# Logic_controller.net
KiCad netlist of a schematic drawn in Altium Designer
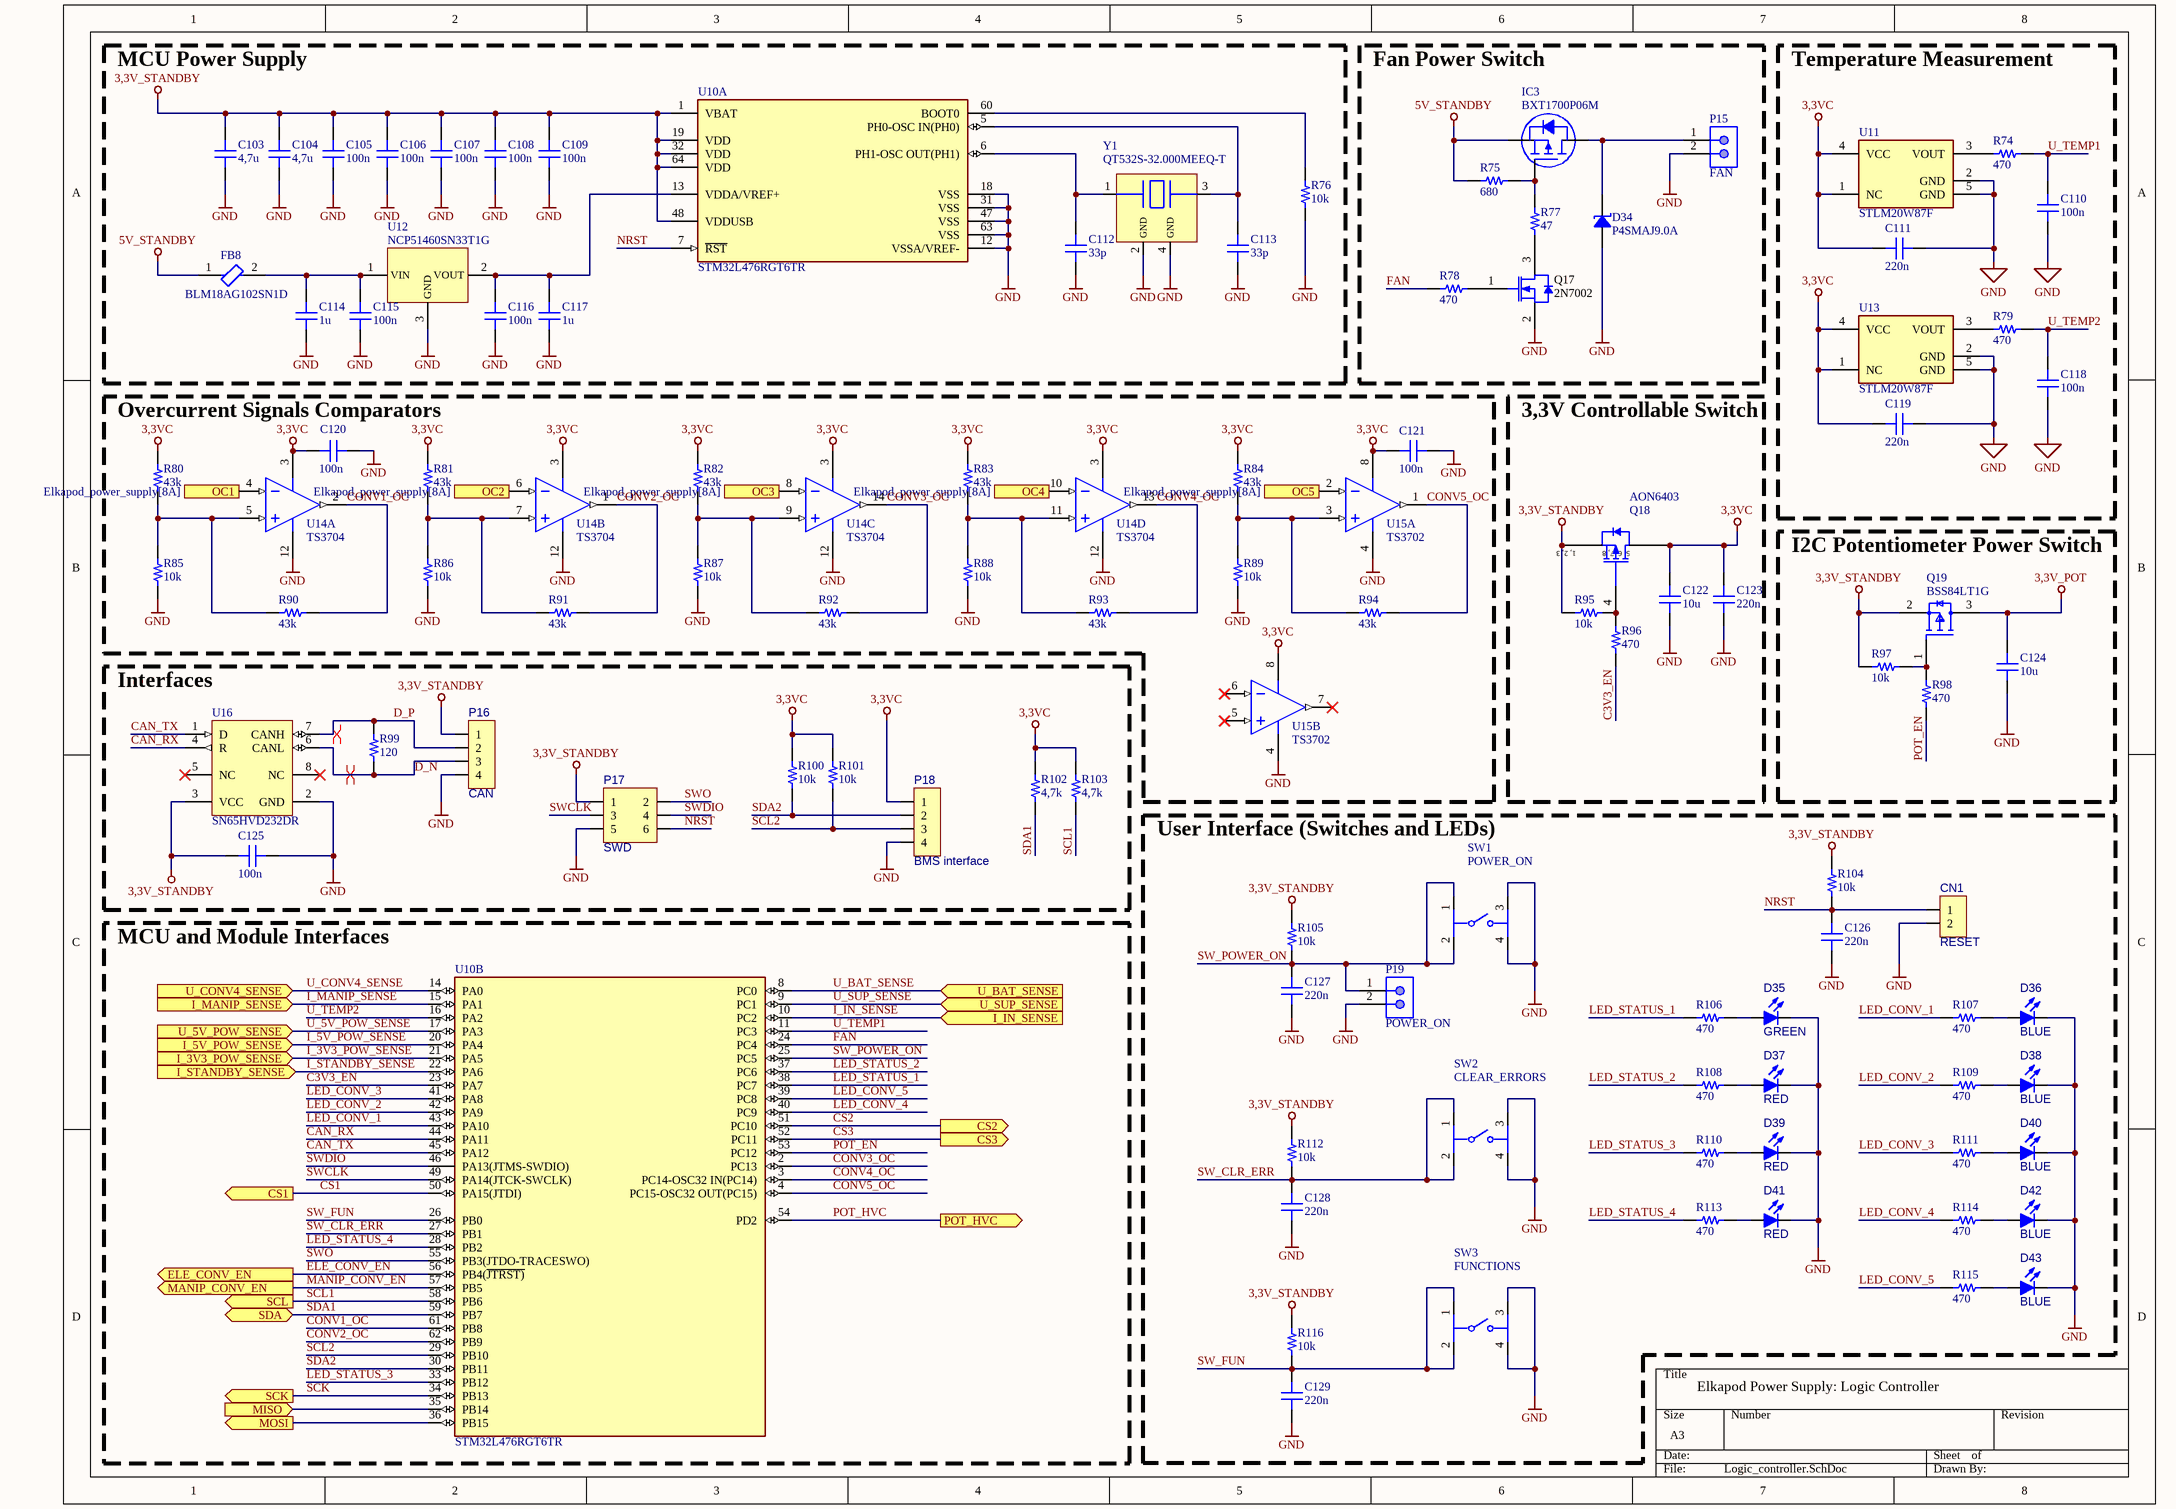
[diagram p0: Logic_controller.SchDoc]

(export (version "E")
  (design (tool "Eeschema 10.0.6"))
  (components
    (comp (ref "C103")
      (value "4,7u")
      (footprint "CAP 0603_1608")
      (description "CAP CER 4,7uF 25V X5R 0603")
      (fields (field (name "PART NUMBER") "C0603C272F3GAC7867") (field (name "MANUFACTURER") "KEMET"))
      (libsource (lib "Celestial Altium Library - altium_library") (part "Capacitor"))
    )
    (comp (ref "C104")
      (value "4,7u")
      (footprint "CAP 0603_1608")
      (description "CAP CER 4,7uF 25V X5R 0603")
      (fields (field (name "PART NUMBER") "C0603C272F3GAC7867") (field (name "MANUFACTURER") "KEMET"))
      (libsource (lib "Celestial Altium Library - altium_library") (part "Capacitor"))
    )
    (comp (ref "C105")
      (value "100n")
      (footprint "CAP 0603_1608")
      (description "CAP CER 100nF 25V X5R 0603")
      (fields (field (name "PART NUMBER") "C0603C272F3GAC7867") (field (name "MANUFACTURER") "KEMET"))
      (libsource (lib "Celestial Altium Library - altium_library") (part "Capacitor"))
    )
    (comp (ref "C106")
      (value "100n")
      (footprint "CAP 0603_1608")
      (description "CAP CER 100nF 25V X5R 0603")
      (fields (field (name "PART NUMBER") "C0603C272F3GAC7867") (field (name "MANUFACTURER") "KEMET"))
      (libsource (lib "Celestial Altium Library - altium_library") (part "Capacitor"))
    )
    (comp (ref "C107")
      (value "100n")
      (footprint "CAP 0603_1608")
      (description "CAP CER 100nF 25V X5R 0603")
      (fields (field (name "PART NUMBER") "C0603C272F3GAC7867") (field (name "MANUFACTURER") "KEMET"))
      (libsource (lib "Celestial Altium Library - altium_library") (part "Capacitor"))
    )
    (comp (ref "C108")
      (value "100n")
      (footprint "CAP 0603_1608")
      (description "CAP CER 100nF 25V X5R 0603")
      (fields (field (name "PART NUMBER") "C0603C272F3GAC7867") (field (name "MANUFACTURER") "KEMET"))
      (libsource (lib "Celestial Altium Library - altium_library") (part "Capacitor"))
    )
    (comp (ref "C109")
      (value "100n")
      (footprint "CAP 0603_1608")
      (description "CAP CER 100nF 25V X5R 0603")
      (fields (field (name "PART NUMBER") "C0603C272F3GAC7867") (field (name "MANUFACTURER") "KEMET"))
      (libsource (lib "Celestial Altium Library - altium_library") (part "Capacitor"))
    )
    (comp (ref "C110")
      (value "100n")
      (footprint "CAP 0603_1608")
      (description "CAP CER 100nF 25V X5R 0603")
      (fields (field (name "PART NUMBER") "C0603C272F3GAC7867") (field (name "MANUFACTURER") "KEMET"))
      (libsource (lib "Celestial Altium Library - altium_library") (part "Capacitor"))
    )
    (comp (ref "C111")
      (value "220n")
      (footprint "CAP 0603_1608")
      (description "CAP CER 220nF 25V X5R 0603")
      (fields (field (name "PART NUMBER") "C0603C272F3GAC7867") (field (name "MANUFACTURER") "KEMET"))
      (libsource (lib "Celestial Altium Library - altium_library") (part "Capacitor"))
    )
    (comp (ref "C112")
      (value "33p")
      (footprint "CAP 0603_1608")
      (description "CAP CER 33pF 50V G0C 0603")
      (fields (field (name "PART NUMBER") "C0603C272F3GAC7867") (field (name "MANUFACTURER") "KEMET"))
      (libsource (lib "Celestial Altium Library - altium_library") (part "Capacitor"))
    )
    (comp (ref "C113")
      (value "33p")
      (footprint "CAP 0603_1608")
      (description "CAP CER 33pF 50V G0C 0603")
      (fields (field (name "PART NUMBER") "C0603C272F3GAC7867") (field (name "MANUFACTURER") "KEMET"))
      (libsource (lib "Celestial Altium Library - altium_library") (part "Capacitor"))
    )
    (comp (ref "C114")
      (value "1u")
      (footprint "CAP 0603_1608")
      (description "CAP CER 1uF 16V X5R 0603")
      (fields (field (name "PART NUMBER") "C0603C272F3GAC7867") (field (name "MANUFACTURER") "KEMET"))
      (libsource (lib "Celestial Altium Library - altium_library") (part "Capacitor"))
    )
    (comp (ref "C115")
      (value "100n")
      (footprint "CAP 0603_1608")
      (description "CAP CER 100nF 25V X5R 0603")
      (fields (field (name "PART NUMBER") "C0603C272F3GAC7867") (field (name "MANUFACTURER") "KEMET"))
      (libsource (lib "Celestial Altium Library - altium_library") (part "Capacitor"))
    )
    (comp (ref "C116")
      (value "100n")
      (footprint "CAP 0603_1608")
      (description "CAP CER 100nF 25V X5R 0603")
      (fields (field (name "PART NUMBER") "C0603C272F3GAC7867") (field (name "MANUFACTURER") "KEMET"))
      (libsource (lib "Celestial Altium Library - altium_library") (part "Capacitor"))
    )
    (comp (ref "C117")
      (value "1u")
      (footprint "CAP 0603_1608")
      (description "CAP CER 1uF 16V X5R 0603")
      (fields (field (name "PART NUMBER") "C0603C272F3GAC7867") (field (name "MANUFACTURER") "KEMET"))
      (libsource (lib "Celestial Altium Library - altium_library") (part "Capacitor"))
    )
    (comp (ref "C118")
      (value "100n")
      (footprint "CAP 0603_1608")
      (description "CAP CER 100nF 25V X5R 0603")
      (fields (field (name "PART NUMBER") "C0603C272F3GAC7867") (field (name "MANUFACTURER") "KEMET"))
      (libsource (lib "Celestial Altium Library - altium_library") (part "Capacitor"))
    )
    (comp (ref "C119")
      (value "220n")
      (footprint "CAP 0603_1608")
      (description "CAP CER 220nF 25V X5R 0603")
      (fields (field (name "PART NUMBER") "C0603C272F3GAC7867") (field (name "MANUFACTURER") "KEMET"))
      (libsource (lib "Celestial Altium Library - altium_library") (part "Capacitor"))
    )
    (comp (ref "C120")
      (value "100n")
      (footprint "CAP 0603_1608")
      (description "CAP CER 100nF 25V X5R 0603")
      (fields (field (name "PART NUMBER") "C0603C272F3GAC7867") (field (name "MANUFACTURER") "KEMET"))
      (libsource (lib "Celestial Altium Library - altium_library") (part "Capacitor"))
    )
    (comp (ref "C121")
      (value "100n")
      (footprint "CAP 0603_1608")
      (description "CAP CER 100nF 25V X5R 0603")
      (fields (field (name "PART NUMBER") "C0603C272F3GAC7867") (field (name "MANUFACTURER") "KEMET"))
      (libsource (lib "Celestial Altium Library - altium_library") (part "Capacitor"))
    )
    (comp (ref "C122")
      (value "10u")
      (footprint "CAP 0603_1608")
      (description "CAP CER 10uF 35V X5R 0603")
      (fields (field (name "PART NUMBER") "C0603C272F3GAC7867") (field (name "MANUFACTURER") "KEMET"))
      (libsource (lib "Celestial Altium Library - altium_library") (part "Capacitor"))
    )
    (comp (ref "C123")
      (value "220n")
      (footprint "CAP 0603_1608")
      (description "CAP CER 220nF 25V X5R 0603")
      (fields (field (name "PART NUMBER") "C0603C272F3GAC7867") (field (name "MANUFACTURER") "KEMET"))
      (libsource (lib "Celestial Altium Library - altium_library") (part "Capacitor"))
    )
    (comp (ref "C124")
      (value "10u")
      (footprint "CAP 0603_1608")
      (description "CAP CER 10uF 35V X5R 0603")
      (fields (field (name "PART NUMBER") "C0603C272F3GAC7867") (field (name "MANUFACTURER") "KEMET"))
      (libsource (lib "Celestial Altium Library - altium_library") (part "Capacitor"))
    )
    (comp (ref "C125")
      (value "100n")
      (footprint "CAP 0603_1608")
      (description "CAP CER 100nF 25V X5R 0603")
      (fields (field (name "PART NUMBER") "C0603C272F3GAC7867") (field (name "MANUFACTURER") "KEMET"))
      (libsource (lib "Celestial Altium Library - altium_library") (part "Capacitor"))
    )
    (comp (ref "C126")
      (value "220n")
      (footprint "CAP 0603_1608")
      (description "CAP CER 220nF 25V X5R 0603")
      (fields (field (name "PART NUMBER") "C0603C272F3GAC7867") (field (name "MANUFACTURER") "KEMET"))
      (libsource (lib "Celestial Altium Library - altium_library") (part "Capacitor"))
    )
    (comp (ref "C127")
      (value "220n")
      (footprint "CAP 0603_1608")
      (description "CAP CER 220nF 25V X5R 0603")
      (fields (field (name "PART NUMBER") "C0603C272F3GAC7867") (field (name "MANUFACTURER") "KEMET"))
      (libsource (lib "Celestial Altium Library - altium_library") (part "Capacitor"))
    )
    (comp (ref "C128")
      (value "220n")
      (footprint "CAP 0603_1608")
      (description "CAP CER 220nF 25V X5R 0603")
      (fields (field (name "PART NUMBER") "C0603C272F3GAC7867") (field (name "MANUFACTURER") "KEMET"))
      (libsource (lib "Celestial Altium Library - altium_library") (part "Capacitor"))
    )
    (comp (ref "C129")
      (value "220n")
      (footprint "CAP 0603_1608")
      (description "CAP CER 220nF 25V X5R 0603")
      (fields (field (name "PART NUMBER") "C0603C272F3GAC7867") (field (name "MANUFACTURER") "KEMET"))
      (libsource (lib "Celestial Altium Library - altium_library") (part "Capacitor"))
    )
    (comp (ref "CN1") (value "RESET") (footprint "GP_2x1") (libsource (lib "goldpin_male") (part "CN_2x1")))
    (comp (ref "D34")
      (value "P4SMAJ9.0A")
      (footprint "DO214AC SMA")
      (description "TVS DIODE 9VDC DO214AC")
      (libsource (lib "Celestial Altium Library - altium_library") (part "DIODE TVS UNI"))
    )
    (comp (ref "D35")
      (value "GREEN")
      (footprint "LED0805B")
      (description "GREEN LED")
      (libsource (lib "leds") (part "LED_BLUE"))
    )
    (comp (ref "D36")
      (value "BLUE")
      (footprint "LED0805B")
      (description "BLUE LED")
      (libsource (lib "leds") (part "LED_BLUE"))
    )
    (comp (ref "D37")
      (value "RED")
      (footprint "LED0805B")
      (description "RED LED")
      (libsource (lib "leds") (part "LED_BLUE"))
    )
    (comp (ref "D38")
      (value "BLUE")
      (footprint "LED0805B")
      (description "BLUE LED")
      (libsource (lib "leds") (part "LED_BLUE"))
    )
    (comp (ref "D39")
      (value "RED")
      (footprint "LED0805B")
      (description "RED LED")
      (libsource (lib "leds") (part "LED_BLUE"))
    )
    (comp (ref "D40")
      (value "BLUE")
      (footprint "LED0805B")
      (description "BLUE LED")
      (libsource (lib "leds") (part "LED_BLUE"))
    )
    (comp (ref "D41")
      (value "RED")
      (footprint "LED0805B")
      (description "RED LED")
      (libsource (lib "leds") (part "LED_BLUE"))
    )
    (comp (ref "D42")
      (value "BLUE")
      (footprint "LED0805B")
      (description "BLUE LED")
      (libsource (lib "leds") (part "LED_BLUE"))
    )
    (comp (ref "D43")
      (value "BLUE")
      (footprint "LED0805B")
      (description "BLUE LED")
      (libsource (lib "leds") (part "LED_BLUE"))
    )
    (comp (ref "FB8")
      (value "BLM18AG102SN1D")
      (footprint "FP-BLM18-0_15-t0_8-MFG")
      (description "Chip Ferrite Bead, 0603, 1000Ω @ 100MHz, 0.5Ω, 25%, 450mA")
      (fields (field (name "TOLERANCE") "25%"))
      (libsource (lib "Altium Content Vault") (part "5f30dd21d616792df468990f7003faa"))
    )
    (comp (ref "IC3")
      (value "BXT1700P06M")
      (footprint "ON SEMI SOT-23-3")
      (description "MOSFET P-CH 60V 2.8A SOT-23-3")
      (libsource (lib "Celestial Altium Library - altium_library") (part "ON SEMI MOSFET P-CH SOT-23-3"))
    )
    (comp (ref "P15")
      (value "FAN")
      (footprint "MOLX-22-23-2021_V")
      (fields (field (name "PARTNUMBER") "22-23-2021"))
      (libsource (lib "Altium Content Vault") (part "CN-1P-M-R2"))
    )
    (comp (ref "P16")
      (value "CAN")
      (footprint "KK/2.54/4")
      (description "Connector: PCB-cable; KK; socket; male; PIN:4; straight/right-angle; tinned; THT")
      (libsource (lib "kk") (part "CN_4x1"))
    )
    (comp (ref "P17") (value "SWD") (footprint "GP_3x2") (libsource (lib "goldpin_male") (part "CN_3x2")))
    (comp (ref "P18")
      (value "BMS interface")
      (footprint "KK/2.54/4")
      (description "Connector: PCB-cable; KK; socket; male; PIN:4; straight/right-angle; tinned; THT")
      (libsource (lib "kk") (part "CN_4x1"))
    )
    (comp (ref "P19")
      (value "POWER_ON")
      (footprint "MOLX-22-23-2021_V")
      (fields (field (name "PARTNUMBER") "22-23-2021"))
      (libsource (lib "Altium Content Vault") (part "CN-1P-M-R2"))
    )
    (comp (ref "Q17")
      (value "2N7002")
      (footprint "INF-PG-SOT23_M")
      (fields (field (name "MANUFACTURER") "Infineon"))
      (libsource (lib "Altium Content Vault") (part "INF-NDMOS-GSD-3"))
    )
    (comp (ref "Q18")
      (value "AON6403")
      (footprint "DFN5x6")
      (description "P-MOSFET; 67A; 30V; DFN5x6")
      (libsource (lib "My_transistors") (part "AON6403"))
    )
    (comp (ref "Q19")
      (value "BSS84LT1G")
      (footprint "FP-318-08-IPC_A")
      (description "MOSFET P-CH 50V 130MA SOT-23")
      (libsource (lib "Altium Content Vault") (part "1317a8eff0fddff9cd18bdaa032127a"))
    )
    (comp (ref "R74")
      (value "470")
      (footprint "RES 0603_1608")
      (description "RES 470 OHM 1% 0,1W 0603")
      (fields
        (field (name "PART NUMBER") "RNCS0603BKE10K0")
        (field (name "MANUFACTURER") "Stackpole Electronics Inc")
      )
      (libsource (lib "Celestial Altium Library - altium_library") (part "Resistor"))
    )
    (comp (ref "R75")
      (value "680")
      (footprint "RES 0603_1608")
      (description "RES 680 OHM 1% 0,1W 0603")
      (fields
        (field (name "PART NUMBER") "RNCS0603BKE10K0")
        (field (name "MANUFACTURER") "Stackpole Electronics Inc")
      )
      (libsource (lib "Celestial Altium Library - altium_library") (part "Resistor"))
    )
    (comp (ref "R76")
      (value "10k")
      (footprint "RES 0603_1608")
      (description "RES 10K OHM 1% 0,1W 0603")
      (fields
        (field (name "PART NUMBER") "RNCS0603BKE10K0")
        (field (name "MANUFACTURER") "Stackpole Electronics Inc")
      )
      (libsource (lib "Celestial Altium Library - altium_library") (part "Resistor"))
    )
    (comp (ref "R77")
      (value "47")
      (footprint "RES 0603_1608")
      (description "RES 47 OHM 1% 0,1W 0603")
      (fields
        (field (name "PART NUMBER") "RNCS0603BKE10K0")
        (field (name "MANUFACTURER") "Stackpole Electronics Inc")
      )
      (libsource (lib "Celestial Altium Library - altium_library") (part "Resistor"))
    )
    (comp (ref "R78")
      (value "470")
      (footprint "RES 0603_1608")
      (description "RES 470 OHM 1% 0,1W 0603")
      (fields
        (field (name "PART NUMBER") "RNCS0603BKE10K0")
        (field (name "MANUFACTURER") "Stackpole Electronics Inc")
      )
      (libsource (lib "Celestial Altium Library - altium_library") (part "Resistor"))
    )
    (comp (ref "R79")
      (value "470")
      (footprint "RES 0603_1608")
      (description "RES 470 OHM 1% 0,1W 0603")
      (fields
        (field (name "PART NUMBER") "RNCS0603BKE10K0")
        (field (name "MANUFACTURER") "Stackpole Electronics Inc")
      )
      (libsource (lib "Celestial Altium Library - altium_library") (part "Resistor"))
    )
    (comp (ref "R80")
      (value "43k")
      (footprint "RES 0603_1608")
      (description "RES 43K OHM 1% 0,1W 0603")
      (fields
        (field (name "PART NUMBER") "RNCS0603BKE10K0")
        (field (name "MANUFACTURER") "Stackpole Electronics Inc")
      )
      (libsource (lib "Celestial Altium Library - altium_library") (part "Resistor"))
    )
    (comp (ref "R81")
      (value "43k")
      (footprint "RES 0603_1608")
      (description "RES 43K OHM 1% 0,1W 0603")
      (fields
        (field (name "PART NUMBER") "RNCS0603BKE10K0")
        (field (name "MANUFACTURER") "Stackpole Electronics Inc")
      )
      (libsource (lib "Celestial Altium Library - altium_library") (part "Resistor"))
    )
    (comp (ref "R82")
      (value "43k")
      (footprint "RES 0603_1608")
      (description "RES 43K OHM 1% 0,1W 0603")
      (fields
        (field (name "PART NUMBER") "RNCS0603BKE10K0")
        (field (name "MANUFACTURER") "Stackpole Electronics Inc")
      )
      (libsource (lib "Celestial Altium Library - altium_library") (part "Resistor"))
    )
    (comp (ref "R83")
      (value "43k")
      (footprint "RES 0603_1608")
      (description "RES 43K OHM 1% 0,1W 0603")
      (fields
        (field (name "PART NUMBER") "RNCS0603BKE10K0")
        (field (name "MANUFACTURER") "Stackpole Electronics Inc")
      )
      (libsource (lib "Celestial Altium Library - altium_library") (part "Resistor"))
    )
    (comp (ref "R84")
      (value "43k")
      (footprint "RES 0603_1608")
      (description "RES 43K OHM 1% 0,1W 0603")
      (fields
        (field (name "PART NUMBER") "RNCS0603BKE10K0")
        (field (name "MANUFACTURER") "Stackpole Electronics Inc")
      )
      (libsource (lib "Celestial Altium Library - altium_library") (part "Resistor"))
    )
    (comp (ref "R85")
      (value "10k")
      (footprint "RES 0603_1608")
      (description "RES 10K OHM 1% 0,1W 0603")
      (fields
        (field (name "PART NUMBER") "RNCS0603BKE10K0")
        (field (name "MANUFACTURER") "Stackpole Electronics Inc")
      )
      (libsource (lib "Celestial Altium Library - altium_library") (part "Resistor"))
    )
    (comp (ref "R86")
      (value "10k")
      (footprint "RES 0603_1608")
      (description "RES 10K OHM 1% 0,1W 0603")
      (fields
        (field (name "PART NUMBER") "RNCS0603BKE10K0")
        (field (name "MANUFACTURER") "Stackpole Electronics Inc")
      )
      (libsource (lib "Celestial Altium Library - altium_library") (part "Resistor"))
    )
    (comp (ref "R87")
      (value "10k")
      (footprint "RES 0603_1608")
      (description "RES 10K OHM 1% 0,1W 0603")
      (fields
        (field (name "PART NUMBER") "RNCS0603BKE10K0")
        (field (name "MANUFACTURER") "Stackpole Electronics Inc")
      )
      (libsource (lib "Celestial Altium Library - altium_library") (part "Resistor"))
    )
    (comp (ref "R88")
      (value "10k")
      (footprint "RES 0603_1608")
      (description "RES 10K OHM 1% 0,1W 0603")
      (fields
        (field (name "PART NUMBER") "RNCS0603BKE10K0")
        (field (name "MANUFACTURER") "Stackpole Electronics Inc")
      )
      (libsource (lib "Celestial Altium Library - altium_library") (part "Resistor"))
    )
    (comp (ref "R89")
      (value "10k")
      (footprint "RES 0603_1608")
      (description "RES 10K OHM 1% 0,1W 0603")
      (fields
        (field (name "PART NUMBER") "RNCS0603BKE10K0")
        (field (name "MANUFACTURER") "Stackpole Electronics Inc")
      )
      (libsource (lib "Celestial Altium Library - altium_library") (part "Resistor"))
    )
    (comp (ref "R90")
      (value "43k")
      (footprint "RES 0603_1608")
      (description "RES 43K OHM 1% 0,1W 0603")
      (fields
        (field (name "PART NUMBER") "RNCS0603BKE10K0")
        (field (name "MANUFACTURER") "Stackpole Electronics Inc")
      )
      (libsource (lib "Celestial Altium Library - altium_library") (part "Resistor"))
    )
    (comp (ref "R91")
      (value "43k")
      (footprint "RES 0603_1608")
      (description "RES 43K OHM 1% 0,1W 0603")
      (fields
        (field (name "PART NUMBER") "RNCS0603BKE10K0")
        (field (name "MANUFACTURER") "Stackpole Electronics Inc")
      )
      (libsource (lib "Celestial Altium Library - altium_library") (part "Resistor"))
    )
    (comp (ref "R92")
      (value "43k")
      (footprint "RES 0603_1608")
      (description "RES 43K OHM 1% 0,1W 0603")
      (fields
        (field (name "PART NUMBER") "RNCS0603BKE10K0")
        (field (name "MANUFACTURER") "Stackpole Electronics Inc")
      )
      (libsource (lib "Celestial Altium Library - altium_library") (part "Resistor"))
    )
    (comp (ref "R93")
      (value "43k")
      (footprint "RES 0603_1608")
      (description "RES 43K OHM 1% 0,1W 0603")
      (fields
        (field (name "PART NUMBER") "RNCS0603BKE10K0")
        (field (name "MANUFACTURER") "Stackpole Electronics Inc")
      )
      (libsource (lib "Celestial Altium Library - altium_library") (part "Resistor"))
    )
    (comp (ref "R94")
      (value "43k")
      (footprint "RES 0603_1608")
      (description "RES 43K OHM 1% 0,1W 0603")
      (fields
        (field (name "PART NUMBER") "RNCS0603BKE10K0")
        (field (name "MANUFACTURER") "Stackpole Electronics Inc")
      )
      (libsource (lib "Celestial Altium Library - altium_library") (part "Resistor"))
    )
    (comp (ref "R95")
      (value "10k")
      (footprint "RES 0603_1608")
      (description "RES 10K OHM 1% 0,1W 0603")
      (fields
        (field (name "PART NUMBER") "RNCS0603BKE10K0")
        (field (name "MANUFACTURER") "Stackpole Electronics Inc")
      )
      (libsource (lib "Celestial Altium Library - altium_library") (part "Resistor"))
    )
    (comp (ref "R96")
      (value "470")
      (footprint "RES 0603_1608")
      (description "RES 470 OHM 1% 0,1W 0603")
      (fields
        (field (name "PART NUMBER") "RNCS0603BKE10K0")
        (field (name "MANUFACTURER") "Stackpole Electronics Inc")
      )
      (libsource (lib "Celestial Altium Library - altium_library") (part "Resistor"))
    )
    (comp (ref "R97")
      (value "10k")
      (footprint "RES 0603_1608")
      (description "RES 10K OHM 1% 0,1W 0603")
      (fields
        (field (name "PART NUMBER") "RNCS0603BKE10K0")
        (field (name "MANUFACTURER") "Stackpole Electronics Inc")
      )
      (libsource (lib "Celestial Altium Library - altium_library") (part "Resistor"))
    )
    (comp (ref "R98")
      (value "470")
      (footprint "RES 0603_1608")
      (description "RES 470 OHM 1% 0,1W 0603")
      (fields
        (field (name "PART NUMBER") "RNCS0603BKE10K0")
        (field (name "MANUFACTURER") "Stackpole Electronics Inc")
      )
      (libsource (lib "Celestial Altium Library - altium_library") (part "Resistor"))
    )
    (comp (ref "R99")
      (value "120")
      (footprint "RES 0603_1608")
      (description "RES 120 OHM 1% 0,1W 0603")
      (fields
        (field (name "PART NUMBER") "RNCS0603BKE10K0")
        (field (name "MANUFACTURER") "Stackpole Electronics Inc")
      )
      (libsource (lib "Celestial Altium Library - altium_library") (part "Resistor"))
    )
    (comp (ref "R100")
      (value "10k")
      (footprint "RES 0603_1608")
      (description "RES 10K OHM 1% 0,1W 0603")
      (fields
        (field (name "PART NUMBER") "RNCS0603BKE10K0")
        (field (name "MANUFACTURER") "Stackpole Electronics Inc")
      )
      (libsource (lib "Celestial Altium Library - altium_library") (part "Resistor"))
    )
    (comp (ref "R101")
      (value "10k")
      (footprint "RES 0603_1608")
      (description "RES 10K OHM 1% 0,1W 0603")
      (fields
        (field (name "PART NUMBER") "RNCS0603BKE10K0")
        (field (name "MANUFACTURER") "Stackpole Electronics Inc")
      )
      (libsource (lib "Celestial Altium Library - altium_library") (part "Resistor"))
    )
    (comp (ref "R102")
      (value "4,7k")
      (footprint "RES 0603_1608")
      (description "RES 4,7K OHM 1% 0,1W 0603")
      (fields
        (field (name "PART NUMBER") "RNCS0603BKE10K0")
        (field (name "MANUFACTURER") "Stackpole Electronics Inc")
      )
      (libsource (lib "Celestial Altium Library - altium_library") (part "Resistor"))
    )
    (comp (ref "R103")
      (value "4,7k")
      (footprint "RES 0603_1608")
      (description "RES 4,7K OHM 1% 0,1W 0603")
      (fields
        (field (name "PART NUMBER") "RNCS0603BKE10K0")
        (field (name "MANUFACTURER") "Stackpole Electronics Inc")
      )
      (libsource (lib "Celestial Altium Library - altium_library") (part "Resistor"))
    )
    (comp (ref "R104")
      (value "10k")
      (footprint "RES 0603_1608")
      (description "RES 10K OHM 1% 0,1W 0603")
      (fields
        (field (name "PART NUMBER") "RNCS0603BKE10K0")
        (field (name "MANUFACTURER") "Stackpole Electronics Inc")
      )
      (libsource (lib "Celestial Altium Library - altium_library") (part "Resistor"))
    )
    (comp (ref "R105")
      (value "10k")
      (footprint "RES 0603_1608")
      (description "RES 10K OHM 1% 0,1W 0603")
      (fields
        (field (name "PART NUMBER") "RNCS0603BKE10K0")
        (field (name "MANUFACTURER") "Stackpole Electronics Inc")
      )
      (libsource (lib "Celestial Altium Library - altium_library") (part "Resistor"))
    )
    (comp (ref "R106")
      (value "470")
      (footprint "RES 0603_1608")
      (description "RES 470 OHM 1% 0,1W 0603")
      (fields
        (field (name "PART NUMBER") "RNCS0603BKE10K0")
        (field (name "MANUFACTURER") "Stackpole Electronics Inc")
      )
      (libsource (lib "Celestial Altium Library - altium_library") (part "Resistor"))
    )
    (comp (ref "R107")
      (value "470")
      (footprint "RES 0603_1608")
      (description "RES 470 OHM 1% 0,1W 0603")
      (fields
        (field (name "PART NUMBER") "RNCS0603BKE10K0")
        (field (name "MANUFACTURER") "Stackpole Electronics Inc")
      )
      (libsource (lib "Celestial Altium Library - altium_library") (part "Resistor"))
    )
    (comp (ref "R108")
      (value "470")
      (footprint "RES 0603_1608")
      (description "RES 470 OHM 1% 0,1W 0603")
      (fields
        (field (name "PART NUMBER") "RNCS0603BKE10K0")
        (field (name "MANUFACTURER") "Stackpole Electronics Inc")
      )
      (libsource (lib "Celestial Altium Library - altium_library") (part "Resistor"))
    )
    (comp (ref "R109")
      (value "470")
      (footprint "RES 0603_1608")
      (description "RES 470 OHM 1% 0,1W 0603")
      (fields
        (field (name "PART NUMBER") "RNCS0603BKE10K0")
        (field (name "MANUFACTURER") "Stackpole Electronics Inc")
      )
      (libsource (lib "Celestial Altium Library - altium_library") (part "Resistor"))
    )
    (comp (ref "R110")
      (value "470")
      (footprint "RES 0603_1608")
      (description "RES 470 OHM 1% 0,1W 0603")
      (fields
        (field (name "PART NUMBER") "RNCS0603BKE10K0")
        (field (name "MANUFACTURER") "Stackpole Electronics Inc")
      )
      (libsource (lib "Celestial Altium Library - altium_library") (part "Resistor"))
    )
    (comp (ref "R111")
      (value "470")
      (footprint "RES 0603_1608")
      (description "RES 470 OHM 1% 0,1W 0603")
      (fields
        (field (name "PART NUMBER") "RNCS0603BKE10K0")
        (field (name "MANUFACTURER") "Stackpole Electronics Inc")
      )
      (libsource (lib "Celestial Altium Library - altium_library") (part "Resistor"))
    )
    (comp (ref "R112")
      (value "10k")
      (footprint "RES 0603_1608")
      (description "RES 10K OHM 1% 0,1W 0603")
      (fields
        (field (name "PART NUMBER") "RNCS0603BKE10K0")
        (field (name "MANUFACTURER") "Stackpole Electronics Inc")
      )
      (libsource (lib "Celestial Altium Library - altium_library") (part "Resistor"))
    )
    (comp (ref "R113")
      (value "470")
      (footprint "RES 0603_1608")
      (description "RES 470 OHM 1% 0,1W 0603")
      (fields
        (field (name "PART NUMBER") "RNCS0603BKE10K0")
        (field (name "MANUFACTURER") "Stackpole Electronics Inc")
      )
      (libsource (lib "Celestial Altium Library - altium_library") (part "Resistor"))
    )
    (comp (ref "R114")
      (value "470")
      (footprint "RES 0603_1608")
      (description "RES 470 OHM 1% 0,1W 0603")
      (fields
        (field (name "PART NUMBER") "RNCS0603BKE10K0")
        (field (name "MANUFACTURER") "Stackpole Electronics Inc")
      )
      (libsource (lib "Celestial Altium Library - altium_library") (part "Resistor"))
    )
    (comp (ref "R115")
      (value "470")
      (footprint "RES 0603_1608")
      (description "RES 470 OHM 1% 0,1W 0603")
      (fields
        (field (name "PART NUMBER") "RNCS0603BKE10K0")
        (field (name "MANUFACTURER") "Stackpole Electronics Inc")
      )
      (libsource (lib "Celestial Altium Library - altium_library") (part "Resistor"))
    )
    (comp (ref "R116")
      (value "10k")
      (footprint "RES 0603_1608")
      (description "RES 10K OHM 1% 0,1W 0603")
      (fields
        (field (name "PART NUMBER") "RNCS0603BKE10K0")
        (field (name "MANUFACTURER") "Stackpole Electronics Inc")
      )
      (libsource (lib "Celestial Altium Library - altium_library") (part "Resistor"))
    )
    (comp (ref "SW1")
      (value "POWER_ON")
      (footprint "FP-B3FS-1000-MFG")
      (description "SWITCH TACTILE SPST-NO 0.05A 24V")
      (fields
        (field (name "MANUFACTURER") "Omron Electronics Inc-EMC Div")
        (field (name "OCTOPART") "https://octopart.com/b3fs-1000-omron-116581")
      )
      (libsource (lib "Altium Content Vault") (part "b8895f3f4cefb76e1819d2863dba89b"))
    )
    (comp (ref "SW2")
      (value "CLEAR_ERRORS")
      (footprint "FP-B3FS-1000-MFG")
      (description "SWITCH TACTILE SPST-NO 0.05A 24V")
      (fields
        (field (name "MANUFACTURER") "Omron Electronics Inc-EMC Div")
        (field (name "OCTOPART") "https://octopart.com/b3fs-1000-omron-116581")
      )
      (libsource (lib "Altium Content Vault") (part "b8895f3f4cefb76e1819d2863dba89b"))
    )
    (comp (ref "SW3")
      (value "FUNCTIONS")
      (footprint "FP-B3FS-1000-MFG")
      (description "SWITCH TACTILE SPST-NO 0.05A 24V")
      (fields
        (field (name "MANUFACTURER") "Omron Electronics Inc-EMC Div")
        (field (name "OCTOPART") "https://octopart.com/b3fs-1000-omron-116581")
      )
      (libsource (lib "Altium Content Vault") (part "b8895f3f4cefb76e1819d2863dba89b"))
    )
    (comp (ref "U10")
      (value "STM32L476RGT6TR")
      (footprint "FP-LQFP64-5W-MFG")
      (description "IC MCU 32BIT 1MB FLASH 64LQFP")
      (fields
        (field (name "OCTOPART") "https://octopart.com/stm32l476rgt6tr-stmicroelectronics-74146120")
        (field (name "MANUFACTURER") "STMicroelectronics")
      )
      (libsource (lib "Altium Content Vault") (part "87b63bd17e71f2d821570a63d08c5bc"))
    )
    (comp (ref "U11")
      (value "STLM20W87F")
      (footprint "FP-SOT323-5L-7091413-MFG")
      (description "SENSOR ANALOG -55C-130C SOT323-5")
      (fields
        (field (name "MANUFACTURER") "STMicroelectronics")
        (field (name "OCTOPART") "https://octopart.com/stlm20w87f-stmicroelectronics-4006294")
      )
      (libsource (lib "Altium Content Vault") (part "0e0d9f6345b04f04d846d3fd79e931c"))
    )
    (comp (ref "U12")
      (value "NCP51460SN33T1G")
      (footprint "SOT23-3")
      (description "Low power precision voltage reference; Iout = 20mA")
      (libsource (lib "My_voltage_regulators") (part "NCP51460SN33T1G"))
    )
    (comp (ref "U13")
      (value "STLM20W87F")
      (footprint "FP-SOT323-5L-7091413-MFG")
      (description "SENSOR ANALOG -55C-130C SOT323-5")
      (fields
        (field (name "MANUFACTURER") "STMicroelectronics")
        (field (name "OCTOPART") "https://octopart.com/stlm20w87f-stmicroelectronics-4006294")
      )
      (libsource (lib "Altium Content Vault") (part "0e0d9f6345b04f04d846d3fd79e931c"))
    )
    (comp (ref "U14")
      (value "TS3704")
      (footprint "SOIC14")
      (description "Micropower push-pusll quad CMOS voltage comparator")
      (libsource (lib "My_integrated_circuits") (part "TS3704"))
    )
    (comp (ref "U15")
      (value "TS3702")
      (footprint "SOIC8")
      (description "Micropower push-pull dual CMOS voltage comparator")
      (libsource (lib "My_integrated_circuits") (part "TS3702"))
    )
    (comp (ref "U16")
      (value "SN65HVD232DR")
      (footprint "D0008A_M")
      (description "3.3 V Can Transceiver, 17 mA, -40 to 85 degC, 8-pin SOIC (D), Green (RoHS & no Sb/Br)")
      (fields (field (name "MANUFACTURER") "Texas Instruments"))
      (libsource (lib "Altium Content Vault") (part "TI-SN65HVD232-SOIC_D-8"))
    )
    (comp (ref "Y1")
      (value "QT532S-32.000MEEQ-T")
      (footprint "QT532S_5,0x3,2_crystal")
      (libsource (lib "My_passive_components") (part "QT532S_CRYSTAL"))
    )
  )
  (nets
    (net (code "1") (name "/C3V3_EN") (class "Default")
      (node (ref "R96") (pin "2") (pinfunction "2_2") (pintype "passive"))
      (node (ref "U10") (pin "23") (pinfunction "PA7_23") (pintype "bidirectional"))
    )
    (net (code "2") (name "/CAN_RX") (class "Default")
      (node (ref "U10") (pin "44") (pinfunction "PA11_44") (pintype "bidirectional"))
      (node (ref "U16") (pin "4") (pinfunction "R_4") (pintype "output"))
    )
    (net (code "3") (name "/CAN_TX") (class "Default")
      (node (ref "U10") (pin "45") (pinfunction "PA12_45") (pintype "bidirectional"))
      (node (ref "U16") (pin "1") (pinfunction "D_1") (pintype "input"))
    )
    (net (code "4") (name "/CONV1_OC") (class "Default")
      (node (ref "R90") (pin "2") (pinfunction "2_2") (pintype "passive"))
      (node (ref "U10") (pin "61") (pinfunction "PB8_61") (pintype "bidirectional"))
      (node (ref "U14") (pin "2") (pinfunction "OUT1_2") (pintype "output"))
    )
    (net (code "5") (name "/CONV2_OC") (class "Default")
      (node (ref "R91") (pin "1") (pinfunction "1_1") (pintype "passive"))
      (node (ref "U10") (pin "62") (pinfunction "PB9_62") (pintype "bidirectional"))
      (node (ref "U14") (pin "1") (pinfunction "OUT2_1") (pintype "output"))
    )
    (net (code "6") (name "/CONV3_OC") (class "Default")
      (node (ref "R92") (pin "1") (pinfunction "1_1") (pintype "passive"))
      (node (ref "U10") (pin "2") (pinfunction "PC13_2") (pintype "bidirectional"))
      (node (ref "U14") (pin "14") (pinfunction "OUT3_14") (pintype "output"))
    )
    (net (code "7") (name "/CONV4_OC") (class "Default")
      (node (ref "R93") (pin "1") (pinfunction "1_1") (pintype "passive"))
      (node (ref "U10") (pin "3") (pinfunction "PC14-OSC32_IN(PC14)_3") (pintype "bidirectional"))
      (node (ref "U14") (pin "13") (pinfunction "OUT4_13") (pintype "output"))
    )
    (net (code "8") (name "/CONV5_OC") (class "Default")
      (node (ref "R94") (pin "1") (pinfunction "1_1") (pintype "passive"))
      (node (ref "U10") (pin "4") (pinfunction "PC15-OSC32_OUT(PC15)_4") (pintype "bidirectional"))
      (node (ref "U15") (pin "1") (pinfunction "OUT1_1") (pintype "output"))
    )
    (net (code "9") (name "/CS1") (class "Default")
      (node (ref "U10") (pin "50") (pinfunction "PA15(JTDI)_50") (pintype "bidirectional"))
    )
    (net (code "10") (name "/CS2") (class "Default")
      (node (ref "U10") (pin "51") (pinfunction "PC10_51") (pintype "bidirectional"))
    )
    (net (code "11") (name "/CS3") (class "Default")
      (node (ref "U10") (pin "52") (pinfunction "PC11_52") (pintype "bidirectional"))
    )
    (net (code "12") (name "/D_N") (class "Default")
      (node (ref "P16") (pin "3") (pinfunction "3_3") (pintype "passive"))
      (node (ref "R99") (pin "2") (pinfunction "2_2") (pintype "passive"))
      (node (ref "U16") (pin "6") (pinfunction "CANL_6") (pintype "bidirectional"))
    )
    (net (code "13") (name "/D_P") (class "Default")
      (node (ref "P16") (pin "2") (pinfunction "2_2") (pintype "passive"))
      (node (ref "R99") (pin "1") (pinfunction "1_1") (pintype "passive"))
      (node (ref "U16") (pin "7") (pinfunction "CANH_7") (pintype "bidirectional"))
    )
    (net (code "14") (name "/ELE_CONV_EN") (class "Default")
      (node (ref "U10") (pin "56") (pinfunction "PB4(~{JTRST)}_56") (pintype "bidirectional"))
    )
    (net (code "15") (name "/FAN") (class "Default")
      (node (ref "R78") (pin "1") (pinfunction "1_1") (pintype "passive"))
      (node (ref "U10") (pin "24") (pinfunction "PC4_24") (pintype "bidirectional"))
    )
    (net (code "16") (name "/I_3V3_POW_SENSE") (class "Default")
      (node (ref "U10") (pin "21") (pinfunction "PA5_21") (pintype "bidirectional"))
    )
    (net (code "17") (name "/I_5V_POW_SENSE") (class "Default")
      (node (ref "U10") (pin "20") (pinfunction "PA4_20") (pintype "bidirectional"))
    )
    (net (code "18") (name "/I_IN_SENSE") (class "Default")
      (node (ref "U10") (pin "10") (pinfunction "PC2_10") (pintype "bidirectional"))
    )
    (net (code "19") (name "/I_MANIP_SENSE") (class "Default")
      (node (ref "U10") (pin "15") (pinfunction "PA1_15") (pintype "bidirectional"))
    )
    (net (code "20") (name "/I_STANDBY_SENSE") (class "Default")
      (node (ref "U10") (pin "22") (pinfunction "PA6_22") (pintype "bidirectional"))
    )
    (net (code "21") (name "/LED_CONV_1") (class "Default")
      (node (ref "R107") (pin "2") (pinfunction "2_2") (pintype "passive"))
      (node (ref "U10") (pin "43") (pinfunction "PA10_43") (pintype "bidirectional"))
    )
    (net (code "22") (name "/LED_CONV_2") (class "Default")
      (node (ref "R109") (pin "2") (pinfunction "2_2") (pintype "passive"))
      (node (ref "U10") (pin "42") (pinfunction "PA9_42") (pintype "bidirectional"))
    )
    (net (code "23") (name "/LED_CONV_3") (class "Default")
      (node (ref "R111") (pin "2") (pinfunction "2_2") (pintype "passive"))
      (node (ref "U10") (pin "41") (pinfunction "PA8_41") (pintype "bidirectional"))
    )
    (net (code "24") (name "/LED_CONV_4") (class "Default")
      (node (ref "R114") (pin "2") (pinfunction "2_2") (pintype "passive"))
      (node (ref "U10") (pin "40") (pinfunction "PC9_40") (pintype "bidirectional"))
    )
    (net (code "25") (name "/LED_CONV_5") (class "Default")
      (node (ref "R115") (pin "2") (pinfunction "2_2") (pintype "passive"))
      (node (ref "U10") (pin "39") (pinfunction "PC8_39") (pintype "bidirectional"))
    )
    (net (code "26") (name "/LED_STATUS_1") (class "Default")
      (node (ref "R106") (pin "2") (pinfunction "2_2") (pintype "passive"))
      (node (ref "U10") (pin "38") (pinfunction "PC7_38") (pintype "bidirectional"))
    )
    (net (code "27") (name "/LED_STATUS_2") (class "Default")
      (node (ref "R108") (pin "2") (pinfunction "2_2") (pintype "passive"))
      (node (ref "U10") (pin "37") (pinfunction "PC6_37") (pintype "bidirectional"))
    )
    (net (code "28") (name "/LED_STATUS_3") (class "Default")
      (node (ref "R110") (pin "2") (pinfunction "2_2") (pintype "passive"))
      (node (ref "U10") (pin "33") (pinfunction "PB12_33") (pintype "bidirectional"))
    )
    (net (code "29") (name "/LED_STATUS_4") (class "Default")
      (node (ref "R113") (pin "2") (pinfunction "2_2") (pintype "passive"))
      (node (ref "U10") (pin "28") (pinfunction "PB2_28") (pintype "bidirectional"))
    )
    (net (code "30") (name "/MANIP_CONV_EN") (class "Default")
      (node (ref "U10") (pin "57") (pinfunction "PB5_57") (pintype "bidirectional"))
    )
    (net (code "31") (name "/MISO") (class "Default")
      (node (ref "U10") (pin "35") (pinfunction "PB14_35") (pintype "bidirectional"))
    )
    (net (code "32") (name "/MOSI") (class "Default")
      (node (ref "U10") (pin "36") (pinfunction "PB15_36") (pintype "bidirectional"))
    )
    (net (code "33") (name "/NRST") (class "Default")
      (node (ref "C126") (pin "2") (pinfunction "2_2") (pintype "passive"))
      (node (ref "CN1") (pin "1") (pinfunction "1_1") (pintype "passive"))
      (node (ref "P17") (pin "6") (pinfunction "6_6") (pintype "passive"))
      (node (ref "R104") (pin "2") (pinfunction "2_2") (pintype "passive"))
      (node (ref "U10") (pin "7") (pinfunction "~{RST}_7") (pintype "input"))
    )
    (net (code "34") (name "/OC1") (class "Default")
      (node (ref "U14") (pin "4") (pinfunction "IN1-_4") (pintype "input"))
    )
    (net (code "35") (name "/OC2") (class "Default")
      (node (ref "U14") (pin "6") (pinfunction "IN2-_6") (pintype "input"))
    )
    (net (code "36") (name "/OC3") (class "Default")
      (node (ref "U14") (pin "8") (pinfunction "IN3-_8") (pintype "input"))
    )
    (net (code "37") (name "/OC4") (class "Default")
      (node (ref "U14") (pin "10") (pinfunction "IN4-_10") (pintype "input"))
    )
    (net (code "38") (name "/OC5") (class "Default")
      (node (ref "U15") (pin "2") (pinfunction "IN1-_2") (pintype "input"))
    )
    (net (code "39") (name "/POT_EN") (class "Default")
      (node (ref "R98") (pin "2") (pinfunction "2_2") (pintype "passive"))
      (node (ref "U10") (pin "53") (pinfunction "PC12_53") (pintype "bidirectional"))
    )
    (net (code "40") (name "/POT_HVC") (class "Default")
      (node (ref "U10") (pin "54") (pinfunction "PD2_54") (pintype "bidirectional"))
    )
    (net (code "41") (name "/SCK") (class "Default")
      (node (ref "U10") (pin "34") (pinfunction "PB13_34") (pintype "bidirectional"))
    )
    (net (code "42") (name "/SCL1") (class "Default")
      (node (ref "R103") (pin "2") (pinfunction "2_2") (pintype "passive"))
      (node (ref "U10") (pin "58") (pinfunction "PB6_58") (pintype "bidirectional"))
    )
    (net (code "43") (name "/SCL2") (class "Default")
      (node (ref "P18") (pin "3") (pinfunction "3_3") (pintype "passive"))
      (node (ref "R101") (pin "2") (pinfunction "2_2") (pintype "passive"))
      (node (ref "U10") (pin "29") (pinfunction "PB10_29") (pintype "bidirectional"))
    )
    (net (code "44") (name "/SDA1") (class "Default")
      (node (ref "R102") (pin "2") (pinfunction "2_2") (pintype "passive"))
      (node (ref "U10") (pin "59") (pinfunction "PB7_59") (pintype "bidirectional"))
    )
    (net (code "45") (name "/SDA2") (class "Default")
      (node (ref "P18") (pin "2") (pinfunction "2_2") (pintype "passive"))
      (node (ref "R100") (pin "2") (pinfunction "2_2") (pintype "passive"))
      (node (ref "U10") (pin "30") (pinfunction "PB11_30") (pintype "bidirectional"))
    )
    (net (code "46") (name "/SWCLK") (class "Default")
      (node (ref "P17") (pin "3") (pinfunction "3_3") (pintype "passive"))
      (node (ref "U10") (pin "49") (pinfunction "PA14(JTCK-SWCLK)_49") (pintype "bidirectional"))
    )
    (net (code "47") (name "/SWDIO") (class "Default")
      (node (ref "P17") (pin "4") (pinfunction "4_4") (pintype "passive"))
      (node (ref "U10") (pin "46") (pinfunction "PA13(JTMS-SWDIO)_46") (pintype "power_in"))
    )
    (net (code "48") (name "/SWO") (class "Default")
      (node (ref "P17") (pin "2") (pinfunction "2_2") (pintype "passive"))
      (node (ref "U10") (pin "55") (pinfunction "PB3(JTDO-TRACESWO)_55") (pintype "bidirectional"))
    )
    (net (code "49") (name "/SW_CLR_ERR") (class "Default")
      (node (ref "C128") (pin "2") (pinfunction "2_2") (pintype "passive"))
      (node (ref "R112") (pin "2") (pinfunction "2_2") (pintype "passive"))
      (node (ref "SW2") (pin "1") (pinfunction "1_1") (pintype "passive"))
      (node (ref "SW2") (pin "2") (pinfunction "2_2") (pintype "passive"))
      (node (ref "U10") (pin "27") (pinfunction "PB1_27") (pintype "bidirectional"))
    )
    (net (code "50") (name "/SW_FUN") (class "Default")
      (node (ref "C129") (pin "2") (pinfunction "2_2") (pintype "passive"))
      (node (ref "R116") (pin "2") (pinfunction "2_2") (pintype "passive"))
      (node (ref "SW3") (pin "1") (pinfunction "1_1") (pintype "passive"))
      (node (ref "SW3") (pin "2") (pinfunction "2_2") (pintype "passive"))
      (node (ref "U10") (pin "26") (pinfunction "PB0_26") (pintype "bidirectional"))
    )
    (net (code "51") (name "/SW_POWER_ON") (class "Default")
      (node (ref "C127") (pin "2") (pinfunction "2_2") (pintype "passive"))
      (node (ref "P19") (pin "1") (pinfunction "1_1") (pintype "passive"))
      (node (ref "R105") (pin "2") (pinfunction "2_2") (pintype "passive"))
      (node (ref "SW1") (pin "1") (pinfunction "1_1") (pintype "passive"))
      (node (ref "SW1") (pin "2") (pinfunction "2_2") (pintype "passive"))
      (node (ref "U10") (pin "25") (pinfunction "PC5_25") (pintype "bidirectional"))
    )
    (net (code "52") (name "/U_5V_POW_SENSE") (class "Default")
      (node (ref "U10") (pin "17") (pinfunction "PA3_17") (pintype "bidirectional"))
    )
    (net (code "53") (name "/U_BAT_SENSE") (class "Default")
      (node (ref "U10") (pin "8") (pinfunction "PC0_8") (pintype "bidirectional"))
    )
    (net (code "54") (name "/U_CONV4_SENSE") (class "Default")
      (node (ref "U10") (pin "14") (pinfunction "PA0_14") (pintype "bidirectional"))
    )
    (net (code "55") (name "/U_SUP_SENSE") (class "Default")
      (node (ref "U10") (pin "9") (pinfunction "PC1_9") (pintype "bidirectional"))
    )
    (net (code "56") (name "/U_TEMP1") (class "Default")
      (node (ref "C110") (pin "1") (pinfunction "1_1") (pintype "passive"))
      (node (ref "R74") (pin "2") (pinfunction "2_2") (pintype "passive"))
      (node (ref "U10") (pin "11") (pinfunction "PC3_11") (pintype "bidirectional"))
    )
    (net (code "57") (name "/U_TEMP2") (class "Default")
      (node (ref "C118") (pin "1") (pinfunction "1_1") (pintype "passive"))
      (node (ref "R79") (pin "2") (pinfunction "2_2") (pintype "passive"))
      (node (ref "U10") (pin "16") (pinfunction "PA2_16") (pintype "bidirectional"))
    )
    (net (code "58") (name "3,3VC") (class "Default")
      (node (ref "C111") (pin "2") (pinfunction "2_2") (pintype "passive"))
      (node (ref "C119") (pin "2") (pinfunction "2_2") (pintype "passive"))
      (node (ref "C120") (pin "2") (pinfunction "2_2") (pintype "passive"))
      (node (ref "C121") (pin "2") (pinfunction "2_2") (pintype "passive"))
      (node (ref "C122") (pin "2") (pinfunction "2_2") (pintype "passive"))
      (node (ref "C123") (pin "2") (pinfunction "2_2") (pintype "passive"))
      (node (ref "P18") (pin "1") (pinfunction "1_1") (pintype "passive"))
      (node (ref "Q18") (pin "5-6-7-8") (pinfunction "D_5-6-7-8") (pintype "passive"))
      (node (ref "R100") (pin "1") (pinfunction "1_1") (pintype "passive"))
      (node (ref "R101") (pin "1") (pinfunction "1_1") (pintype "passive"))
      (node (ref "R102") (pin "1") (pinfunction "1_1") (pintype "passive"))
      (node (ref "R103") (pin "1") (pinfunction "1_1") (pintype "passive"))
      (node (ref "R80") (pin "2") (pinfunction "2_2") (pintype "passive"))
      (node (ref "R81") (pin "2") (pinfunction "2_2") (pintype "passive"))
      (node (ref "R82") (pin "2") (pinfunction "2_2") (pintype "passive"))
      (node (ref "R83") (pin "2") (pinfunction "2_2") (pintype "passive"))
      (node (ref "R84") (pin "2") (pinfunction "2_2") (pintype "passive"))
      (node (ref "U11") (pin "1") (pinfunction "NC_1") (pintype "passive"))
      (node (ref "U11") (pin "4") (pinfunction "VCC_4") (pintype "power_in"))
      (node (ref "U13") (pin "1") (pinfunction "NC_1") (pintype "passive"))
      (node (ref "U13") (pin "4") (pinfunction "VCC_4") (pintype "power_in"))
      (node (ref "U14") (pin "3") (pinfunction "V+_3") (pintype "power_in"))
      (node (ref "U15") (pin "8") (pinfunction "V+_8") (pintype "power_in"))
    )
    (net (code "59") (name "3,3V_POT") (class "Default")
      (node (ref "C124") (pin "2") (pinfunction "2_2") (pintype "passive"))
      (node (ref "Q19") (pin "3") (pinfunction "D_3") (pintype "passive"))
    )
    (net (code "60") (name "3,3V_STANDBY") (class "Default")
      (node (ref "C103") (pin "2") (pinfunction "2_2") (pintype "passive"))
      (node (ref "C104") (pin "2") (pinfunction "2_2") (pintype "passive"))
      (node (ref "C105") (pin "2") (pinfunction "2_2") (pintype "passive"))
      (node (ref "C106") (pin "2") (pinfunction "2_2") (pintype "passive"))
      (node (ref "C107") (pin "2") (pinfunction "2_2") (pintype "passive"))
      (node (ref "C108") (pin "2") (pinfunction "2_2") (pintype "passive"))
      (node (ref "C109") (pin "2") (pinfunction "2_2") (pintype "passive"))
      (node (ref "C125") (pin "2") (pinfunction "2_2") (pintype "passive"))
      (node (ref "P16") (pin "1") (pinfunction "1_1") (pintype "passive"))
      (node (ref "P17") (pin "1") (pinfunction "1_1") (pintype "passive"))
      (node (ref "Q18") (pin "1") (pinfunction "S_1") (pintype "passive"))
      (node (ref "Q18") (pin "2") (pinfunction "S_2") (pintype "passive"))
      (node (ref "Q18") (pin "3") (pinfunction "S_3") (pintype "passive"))
      (node (ref "Q19") (pin "2") (pinfunction "S_2") (pintype "passive"))
      (node (ref "R104") (pin "1") (pinfunction "1_1") (pintype "passive"))
      (node (ref "R105") (pin "1") (pinfunction "1_1") (pintype "passive"))
      (node (ref "R112") (pin "1") (pinfunction "1_1") (pintype "passive"))
      (node (ref "R116") (pin "1") (pinfunction "1_1") (pintype "passive"))
      (node (ref "R95") (pin "1") (pinfunction "1_1") (pintype "passive"))
      (node (ref "R97") (pin "1") (pinfunction "1_1") (pintype "passive"))
      (node (ref "U10") (pin "1") (pinfunction "VBAT_1") (pintype "power_in"))
      (node (ref "U10") (pin "19") (pinfunction "VDD_19") (pintype "power_in"))
      (node (ref "U10") (pin "32") (pinfunction "VDD_32") (pintype "power_in"))
      (node (ref "U10") (pin "48") (pinfunction "VDDUSB_48") (pintype "power_in"))
      (node (ref "U10") (pin "64") (pinfunction "VDD_64") (pintype "power_in"))
      (node (ref "U16") (pin "3") (pinfunction "VCC_3") (pintype "power_in"))
    )
    (net (code "61") (name "5V_STANDBY") (class "Default")
      (node (ref "FB8") (pin "1") (pinfunction "1_1") (pintype "passive"))
      (node (ref "IC3") (pin "2") (pinfunction "S_2") (pintype "passive"))
      (node (ref "R75") (pin "1") (pinfunction "1_1") (pintype "passive"))
    )
    (net (code "62") (name "GND") (class "Default")
      (node (ref "C103") (pin "1") (pinfunction "1_1") (pintype "passive"))
      (node (ref "C104") (pin "1") (pinfunction "1_1") (pintype "passive"))
      (node (ref "C105") (pin "1") (pinfunction "1_1") (pintype "passive"))
      (node (ref "C106") (pin "1") (pinfunction "1_1") (pintype "passive"))
      (node (ref "C107") (pin "1") (pinfunction "1_1") (pintype "passive"))
      (node (ref "C108") (pin "1") (pinfunction "1_1") (pintype "passive"))
      (node (ref "C109") (pin "1") (pinfunction "1_1") (pintype "passive"))
      (node (ref "C110") (pin "2") (pinfunction "2_2") (pintype "passive"))
      (node (ref "C111") (pin "1") (pinfunction "1_1") (pintype "passive"))
      (node (ref "C112") (pin "1") (pinfunction "1_1") (pintype "passive"))
      (node (ref "C113") (pin "1") (pinfunction "1_1") (pintype "passive"))
      (node (ref "C114") (pin "1") (pinfunction "1_1") (pintype "passive"))
      (node (ref "C115") (pin "1") (pinfunction "1_1") (pintype "passive"))
      (node (ref "C116") (pin "1") (pinfunction "1_1") (pintype "passive"))
      (node (ref "C117") (pin "1") (pinfunction "1_1") (pintype "passive"))
      (node (ref "C118") (pin "2") (pinfunction "2_2") (pintype "passive"))
      (node (ref "C119") (pin "1") (pinfunction "1_1") (pintype "passive"))
      (node (ref "C120") (pin "1") (pinfunction "1_1") (pintype "passive"))
      (node (ref "C121") (pin "1") (pinfunction "1_1") (pintype "passive"))
      (node (ref "C122") (pin "1") (pinfunction "1_1") (pintype "passive"))
      (node (ref "C123") (pin "1") (pinfunction "1_1") (pintype "passive"))
      (node (ref "C124") (pin "1") (pinfunction "1_1") (pintype "passive"))
      (node (ref "C125") (pin "1") (pinfunction "1_1") (pintype "passive"))
      (node (ref "C126") (pin "1") (pinfunction "1_1") (pintype "passive"))
      (node (ref "C127") (pin "1") (pinfunction "1_1") (pintype "passive"))
      (node (ref "C128") (pin "1") (pinfunction "1_1") (pintype "passive"))
      (node (ref "C129") (pin "1") (pinfunction "1_1") (pintype "passive"))
      (node (ref "CN1") (pin "2") (pinfunction "2_2") (pintype "passive"))
      (node (ref "D34") (pin "1") (pinfunction "1_1") (pintype "passive"))
      (node (ref "D35") (pin "2") (pinfunction "K_2") (pintype "passive"))
      (node (ref "D36") (pin "2") (pinfunction "K_2") (pintype "passive"))
      (node (ref "D37") (pin "2") (pinfunction "K_2") (pintype "passive"))
      (node (ref "D38") (pin "2") (pinfunction "K_2") (pintype "passive"))
      (node (ref "D39") (pin "2") (pinfunction "K_2") (pintype "passive"))
      (node (ref "D40") (pin "2") (pinfunction "K_2") (pintype "passive"))
      (node (ref "D41") (pin "2") (pinfunction "K_2") (pintype "passive"))
      (node (ref "D42") (pin "2") (pinfunction "K_2") (pintype "passive"))
      (node (ref "D43") (pin "2") (pinfunction "K_2") (pintype "passive"))
      (node (ref "P15") (pin "2") (pinfunction "2_2") (pintype "passive"))
      (node (ref "P16") (pin "4") (pinfunction "4_4") (pintype "passive"))
      (node (ref "P17") (pin "5") (pinfunction "5_5") (pintype "passive"))
      (node (ref "P18") (pin "4") (pinfunction "4_4") (pintype "passive"))
      (node (ref "P19") (pin "2") (pinfunction "2_2") (pintype "passive"))
      (node (ref "Q17") (pin "2") (pinfunction "SOURCE_2") (pintype "passive"))
      (node (ref "R76") (pin "2") (pinfunction "2_2") (pintype "passive"))
      (node (ref "R85") (pin "2") (pinfunction "2_2") (pintype "passive"))
      (node (ref "R86") (pin "2") (pinfunction "2_2") (pintype "passive"))
      (node (ref "R87") (pin "2") (pinfunction "2_2") (pintype "passive"))
      (node (ref "R88") (pin "2") (pinfunction "2_2") (pintype "passive"))
      (node (ref "R89") (pin "2") (pinfunction "2_2") (pintype "passive"))
      (node (ref "SW1") (pin "3") (pinfunction "3_3") (pintype "passive"))
      (node (ref "SW1") (pin "4") (pinfunction "4_4") (pintype "passive"))
      (node (ref "SW2") (pin "3") (pinfunction "3_3") (pintype "passive"))
      (node (ref "SW2") (pin "4") (pinfunction "4_4") (pintype "passive"))
      (node (ref "SW3") (pin "3") (pinfunction "3_3") (pintype "passive"))
      (node (ref "SW3") (pin "4") (pinfunction "4_4") (pintype "passive"))
      (node (ref "U10") (pin "12") (pinfunction "VSSA/VREF-_12") (pintype "power_in"))
      (node (ref "U10") (pin "18") (pinfunction "VSS_18") (pintype "power_in"))
      (node (ref "U10") (pin "31") (pinfunction "VSS_31") (pintype "power_in"))
      (node (ref "U10") (pin "47") (pinfunction "VSS_47") (pintype "power_in"))
      (node (ref "U10") (pin "63") (pinfunction "VSS_63") (pintype "power_in"))
      (node (ref "U11") (pin "2") (pinfunction "GND_2") (pintype "power_in"))
      (node (ref "U11") (pin "5") (pinfunction "GND_5") (pintype "power_in"))
      (node (ref "U12") (pin "3") (pinfunction "GND_3") (pintype "passive"))
      (node (ref "U13") (pin "2") (pinfunction "GND_2") (pintype "power_in"))
      (node (ref "U13") (pin "5") (pinfunction "GND_5") (pintype "power_in"))
      (node (ref "U14") (pin "12") (pinfunction "GND_12") (pintype "power_in"))
      (node (ref "U15") (pin "4") (pinfunction "GND_4") (pintype "power_in"))
      (node (ref "U16") (pin "2") (pinfunction "GND_2") (pintype "power_in"))
      (node (ref "Y1") (pin "2") (pinfunction "GND_2") (pintype "passive"))
      (node (ref "Y1") (pin "4") (pinfunction "GND_4") (pintype "passive"))
    )
    (net (code "63") (name "Net-(D35-A)") (class "Default")
      (node (ref "D35") (pin "1") (pinfunction "A_1") (pintype "passive"))
      (node (ref "R106") (pin "1") (pinfunction "1_1") (pintype "passive"))
    )
    (net (code "64") (name "Net-(D36-A)") (class "Default")
      (node (ref "D36") (pin "1") (pinfunction "A_1") (pintype "passive"))
      (node (ref "R107") (pin "1") (pinfunction "1_1") (pintype "passive"))
    )
    (net (code "65") (name "Net-(D37-A)") (class "Default")
      (node (ref "D37") (pin "1") (pinfunction "A_1") (pintype "passive"))
      (node (ref "R108") (pin "1") (pinfunction "1_1") (pintype "passive"))
    )
    (net (code "66") (name "Net-(D38-A)") (class "Default")
      (node (ref "D38") (pin "1") (pinfunction "A_1") (pintype "passive"))
      (node (ref "R109") (pin "1") (pinfunction "1_1") (pintype "passive"))
    )
    (net (code "67") (name "Net-(D39-A)") (class "Default")
      (node (ref "D39") (pin "1") (pinfunction "A_1") (pintype "passive"))
      (node (ref "R110") (pin "1") (pinfunction "1_1") (pintype "passive"))
    )
    (net (code "68") (name "Net-(D40-A)") (class "Default")
      (node (ref "D40") (pin "1") (pinfunction "A_1") (pintype "passive"))
      (node (ref "R111") (pin "1") (pinfunction "1_1") (pintype "passive"))
    )
    (net (code "69") (name "Net-(D41-A)") (class "Default")
      (node (ref "D41") (pin "1") (pinfunction "A_1") (pintype "passive"))
      (node (ref "R113") (pin "1") (pinfunction "1_1") (pintype "passive"))
    )
    (net (code "70") (name "Net-(D42-A)") (class "Default")
      (node (ref "D42") (pin "1") (pinfunction "A_1") (pintype "passive"))
      (node (ref "R114") (pin "1") (pinfunction "1_1") (pintype "passive"))
    )
    (net (code "71") (name "Net-(D43-A)") (class "Default")
      (node (ref "D43") (pin "1") (pinfunction "A_1") (pintype "passive"))
      (node (ref "R115") (pin "1") (pinfunction "1_1") (pintype "passive"))
    )
    (net (code "72") (name "Net-(IC3-D)") (class "Default")
      (node (ref "D34") (pin "2") (pinfunction "2_2") (pintype "passive"))
      (node (ref "IC3") (pin "3") (pinfunction "D_3") (pintype "passive"))
      (node (ref "P15") (pin "1") (pinfunction "1_1") (pintype "passive"))
    )
    (net (code "73") (name "Net-(IC3-G)") (class "Default")
      (node (ref "IC3") (pin "1") (pinfunction "G_1") (pintype "passive"))
      (node (ref "R75") (pin "2") (pinfunction "2_2") (pintype "passive"))
      (node (ref "R77") (pin "1") (pinfunction "1_1") (pintype "passive"))
    )
    (net (code "74") (name "Net-(Q17-DRAIN)") (class "Default")
      (node (ref "Q17") (pin "3") (pinfunction "DRAIN_3") (pintype "passive"))
      (node (ref "R77") (pin "2") (pinfunction "2_2") (pintype "passive"))
    )
    (net (code "75") (name "Net-(Q17-GATE)") (class "Default")
      (node (ref "Q17") (pin "1") (pinfunction "GATE_1") (pintype "passive"))
      (node (ref "R78") (pin "2") (pinfunction "2_2") (pintype "passive"))
    )
    (net (code "76") (name "Net-(Q18-G)") (class "Default")
      (node (ref "Q18") (pin "4") (pinfunction "G_4") (pintype "passive"))
      (node (ref "R95") (pin "2") (pinfunction "2_2") (pintype "passive"))
      (node (ref "R96") (pin "1") (pinfunction "1_1") (pintype "passive"))
    )
    (net (code "77") (name "Net-(Q19-G)") (class "Default")
      (node (ref "Q19") (pin "1") (pinfunction "G_1") (pintype "passive"))
      (node (ref "R97") (pin "2") (pinfunction "2_2") (pintype "passive"))
      (node (ref "R98") (pin "1") (pinfunction "1_1") (pintype "passive"))
    )
    (net (code "78") (name "Net-(U10A-BOOT0)") (class "Default")
      (node (ref "R76") (pin "1") (pinfunction "1_1") (pintype "passive"))
      (node (ref "U10") (pin "60") (pinfunction "BOOT0_60") (pintype "passive"))
    )
    (net (code "79") (name "Net-(U10A-PH0-OSC_IN(PH0))") (class "Default")
      (node (ref "C113") (pin "2") (pinfunction "2_2") (pintype "passive"))
      (node (ref "U10") (pin "5") (pinfunction "PH0-OSC_IN(PH0)_5") (pintype "bidirectional"))
      (node (ref "Y1") (pin "3") (pinfunction "OSC_3") (pintype "passive"))
    )
    (net (code "80") (name "Net-(U10A-PH1-OSC_OUT(PH1))") (class "Default")
      (node (ref "C112") (pin "2") (pinfunction "2_2") (pintype "passive"))
      (node (ref "U10") (pin "6") (pinfunction "PH1-OSC_OUT(PH1)_6") (pintype "bidirectional"))
      (node (ref "Y1") (pin "1") (pinfunction "OSC_1") (pintype "passive"))
    )
    (net (code "81") (name "Net-(U10A-VDDA{slash}VREF+)") (class "Default")
      (node (ref "C116") (pin "2") (pinfunction "2_2") (pintype "passive"))
      (node (ref "C117") (pin "2") (pinfunction "2_2") (pintype "passive"))
      (node (ref "U10") (pin "13") (pinfunction "VDDA/VREF+_13") (pintype "power_in"))
      (node (ref "U12") (pin "2") (pinfunction "VOUT_2") (pintype "passive"))
    )
    (net (code "82") (name "Net-(U11-VOUT)") (class "Default")
      (node (ref "R74") (pin "1") (pinfunction "1_1") (pintype "passive"))
      (node (ref "U11") (pin "3") (pinfunction "VOUT_3") (pintype "passive"))
    )
    (net (code "83") (name "Net-(U12-VIN)") (class "Default")
      (node (ref "C114") (pin "2") (pinfunction "2_2") (pintype "passive"))
      (node (ref "C115") (pin "2") (pinfunction "2_2") (pintype "passive"))
      (node (ref "FB8") (pin "2") (pinfunction "2_2") (pintype "passive"))
      (node (ref "U12") (pin "1") (pinfunction "VIN_1") (pintype "passive"))
    )
    (net (code "84") (name "Net-(U13-VOUT)") (class "Default")
      (node (ref "R79") (pin "1") (pinfunction "1_1") (pintype "passive"))
      (node (ref "U13") (pin "3") (pinfunction "VOUT_3") (pintype "passive"))
    )
    (net (code "85") (name "Net-(U14A-IN1+)") (class "Default")
      (node (ref "R80") (pin "1") (pinfunction "1_1") (pintype "passive"))
      (node (ref "R85") (pin "1") (pinfunction "1_1") (pintype "passive"))
      (node (ref "R90") (pin "1") (pinfunction "1_1") (pintype "passive"))
      (node (ref "U14") (pin "5") (pinfunction "IN1+_5") (pintype "input"))
    )
    (net (code "86") (name "Net-(U14B-IN2+)") (class "Default")
      (node (ref "R81") (pin "1") (pinfunction "1_1") (pintype "passive"))
      (node (ref "R86") (pin "1") (pinfunction "1_1") (pintype "passive"))
      (node (ref "R91") (pin "2") (pinfunction "2_2") (pintype "passive"))
      (node (ref "U14") (pin "7") (pinfunction "IN2+_7") (pintype "input"))
    )
    (net (code "87") (name "Net-(U14C-IN3+)") (class "Default")
      (node (ref "R82") (pin "1") (pinfunction "1_1") (pintype "passive"))
      (node (ref "R87") (pin "1") (pinfunction "1_1") (pintype "passive"))
      (node (ref "R92") (pin "2") (pinfunction "2_2") (pintype "passive"))
      (node (ref "U14") (pin "9") (pinfunction "IN3+_9") (pintype "input"))
    )
    (net (code "88") (name "Net-(U14D-IN4+)") (class "Default")
      (node (ref "R83") (pin "1") (pinfunction "1_1") (pintype "passive"))
      (node (ref "R88") (pin "1") (pinfunction "1_1") (pintype "passive"))
      (node (ref "R93") (pin "2") (pinfunction "2_2") (pintype "passive"))
      (node (ref "U14") (pin "11") (pinfunction "IN4+_11") (pintype "input"))
    )
    (net (code "89") (name "Net-(U15A-IN1+)") (class "Default")
      (node (ref "R84") (pin "1") (pinfunction "1_1") (pintype "passive"))
      (node (ref "R89") (pin "1") (pinfunction "1_1") (pintype "passive"))
      (node (ref "R94") (pin "2") (pinfunction "2_2") (pintype "passive"))
      (node (ref "U15") (pin "3") (pinfunction "IN1+_3") (pintype "input"))
    )
    (net (code "90") (name "unconnected-(U15B-IN2+-Pad5)") (class "Default")
      (node (ref "U15") (pin "5") (pinfunction "IN2+_5") (pintype "input+no_connect"))
    )
    (net (code "91") (name "unconnected-(U15B-IN2--Pad6)") (class "Default")
      (node (ref "U15") (pin "6") (pinfunction "IN2-_6") (pintype "input+no_connect"))
    )
    (net (code "92") (name "unconnected-(U15B-OUT2-Pad7)") (class "Default")
      (node (ref "U15") (pin "7") (pinfunction "OUT2_7") (pintype "output+no_connect"))
    )
    (net (code "93") (name "unconnected-(U16-NC-Pad5)") (class "Default")
      (node (ref "U16") (pin "5") (pinfunction "NC_5") (pintype "passive+no_connect"))
    )
    (net (code "94") (name "unconnected-(U16-NC-Pad8)") (class "Default")
      (node (ref "U16") (pin "8") (pinfunction "NC_8") (pintype "passive+no_connect"))
    )
  )
)
